# Pasa_Bajos.net
KiCad netlist of a schematic drawn in Altium Designer
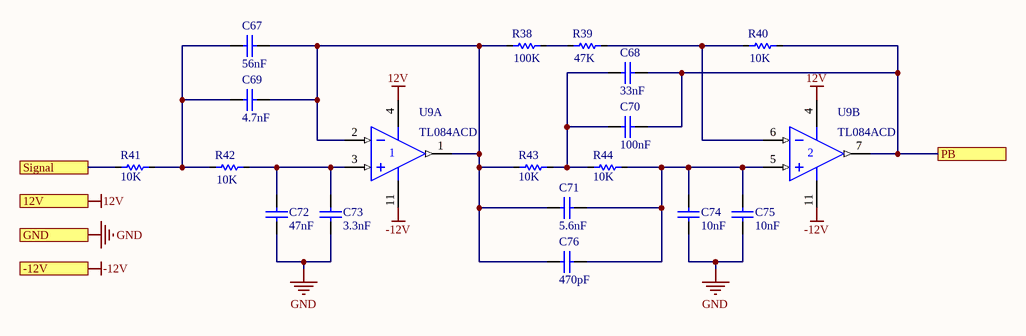
[diagram p0: Pasa Bajos.SchDoc]

(export (version "E")
  (design (tool "Eeschema 10.0.6"))
  (components
    (comp (ref "C67")
      (value "Cap Ceramico Disco")
      (footprint "cap 25")
      (description "Capacitor Ceramico de Insercion")
      (fields (field (name "VALOR") "56nF"))
      (libsource (lib "RUF-Dispositivos-Grales") (part "Cap Ceramico Disco"))
    )
    (comp (ref "C68")
      (value "Cap Ceramico Disco")
      (footprint "cap 10")
      (description "Capacitor Ceramico de Insercion")
      (fields (field (name "VALOR") "33nF"))
      (libsource (lib "RUF-Dispositivos-Grales") (part "Cap Ceramico Disco"))
    )
    (comp (ref "C69")
      (value "Cap Ceramico Disco")
      (footprint "cap 10")
      (description "Capacitor Ceramico de Insercion")
      (fields (field (name "VALOR") "4.7nF"))
      (libsource (lib "RUF-Dispositivos-Grales") (part "Cap Ceramico Disco"))
    )
    (comp (ref "C70")
      (value "Cap Ceramico Disco")
      (footprint "CAP DISCO 200mil")
      (description "Capacitor Ceramico de Insercion")
      (fields (field (name "VALOR") "100nF"))
      (libsource (lib "RUF-Dispositivos-Grales") (part "Cap Ceramico Disco"))
    )
    (comp (ref "C71")
      (value "Cap Ceramico Disco")
      (footprint "CAP DISCO 200mil")
      (description "Capacitor Ceramico de Insercion")
      (fields (field (name "VALOR") "5.6nF"))
      (libsource (lib "RUF-Dispositivos-Grales") (part "Cap Ceramico Disco"))
    )
    (comp (ref "C72")
      (value "Cap Ceramico Disco")
      (footprint "cap 10")
      (description "Capacitor Ceramico de Insercion")
      (fields (field (name "VALOR") "47nF"))
      (libsource (lib "RUF-Dispositivos-Grales") (part "Cap Ceramico Disco"))
    )
    (comp (ref "C73")
      (value "Cap Ceramico Disco")
      (footprint "CAP DISCO 200mil")
      (description "Capacitor Ceramico de Insercion")
      (fields (field (name "VALOR") "3.3nF"))
      (libsource (lib "RUF-Dispositivos-Grales") (part "Cap Ceramico Disco"))
    )
    (comp (ref "C74")
      (value "Cap Ceramico Disco")
      (footprint "CAP DISCO 200mil")
      (description "Capacitor Ceramico de Insercion")
      (fields (field (name "VALOR") "10nF"))
      (libsource (lib "RUF-Dispositivos-Grales") (part "Cap Ceramico Disco"))
    )
    (comp (ref "C75")
      (value "Cap Ceramico Disco")
      (footprint "CAP DISCO 200mil")
      (description "Capacitor Ceramico de Insercion")
      (fields (field (name "VALOR") "10nF"))
      (libsource (lib "RUF-Dispositivos-Grales") (part "Cap Ceramico Disco"))
    )
    (comp (ref "C76")
      (value "Cap Ceramico Disco")
      (footprint "CAP DISCO 200mil")
      (description "Capacitor Ceramico de Insercion")
      (fields (field (name "VALOR") "470pF"))
      (libsource (lib "RUF-Dispositivos-Grales") (part "Cap Ceramico Disco"))
    )
    (comp (ref "R38")
      (value "Res SMD")
      (footprint "RES AXIAL 400mil")
      (description "Res Smd")
      (fields (field (name "VALOR") "100K"))
      (libsource (lib "RUF-Dispositivos-Grales") (part "Res SMD"))
    )
    (comp (ref "R39")
      (value "Res SMD")
      (footprint "1206 resistor")
      (description "Res Smd")
      (fields (field (name "VALOR") "47K"))
      (libsource (lib "RUF-Dispositivos-Grales") (part "Res SMD"))
    )
    (comp (ref "R40")
      (value "Res SMD")
      (footprint "1206 resistor")
      (description "Res Smd")
      (fields (field (name "VALOR") "10K"))
      (libsource (lib "RUF-Dispositivos-Grales") (part "Res SMD"))
    )
    (comp (ref "R41")
      (value "Res SMD")
      (footprint "1206 resistor")
      (description "Res Smd")
      (fields (field (name "VALOR") "10K"))
      (libsource (lib "RUF-Dispositivos-Grales") (part "Res SMD"))
    )
    (comp (ref "R42")
      (value "Res SMD")
      (footprint "1206 resistor")
      (description "Res Smd")
      (fields (field (name "VALOR") "10K"))
      (libsource (lib "RUF-Dispositivos-Grales") (part "Res SMD"))
    )
    (comp (ref "R43")
      (value "Res SMD")
      (footprint "1206 resistor")
      (description "Res Smd")
      (fields (field (name "VALOR") "10K"))
      (libsource (lib "RUF-Dispositivos-Grales") (part "Res SMD"))
    )
    (comp (ref "R44")
      (value "Res SMD")
      (footprint "1206 resistor")
      (description "Res Smd")
      (fields (field (name "VALOR") "10K"))
      (libsource (lib "RUF-Dispositivos-Grales") (part "Res SMD"))
    )
    (comp (ref "U9")
      (value "TL084ACD")
      (footprint "751A-02_N")
      (description "JFET-Input Operational Amplifier")
      (fields (field (name "PUBLISHER") "Altium Limited"))
      (libsource (lib "Motorola Amplifier Operational Amplifier") (part "TL084ACD"))
    )
  )
  (nets
    (net (code "1") (name "-12V") (class "Default")
      (node (ref "U9") (pin "11") (pinfunction "V-_11") (pintype "power_in"))
    )
    (net (code "2") (name "/PB") (class "Default")
      (node (ref "C68") (pin "2") (pinfunction "2_2") (pintype "passive"))
      (node (ref "C70") (pin "2") (pinfunction "2_2") (pintype "passive"))
      (node (ref "R40") (pin "2") (pinfunction "2_2") (pintype "passive"))
      (node (ref "U9") (pin "7") (pinfunction "OUT_7") (pintype "output"))
    )
    (net (code "3") (name "/Signal") (class "Default")
      (node (ref "R41") (pin "1") (pinfunction "1_1") (pintype "passive"))
    )
    (net (code "4") (name "12V") (class "Default")
      (node (ref "U9") (pin "4") (pinfunction "V+_4") (pintype "power_in"))
    )
    (net (code "5") (name "GND") (class "Default")
      (node (ref "C72") (pin "1") (pinfunction "1_1") (pintype "passive"))
      (node (ref "C73") (pin "1") (pinfunction "1_1") (pintype "passive"))
      (node (ref "C74") (pin "2") (pinfunction "2_2") (pintype "passive"))
      (node (ref "C75") (pin "2") (pinfunction "2_2") (pintype "passive"))
    )
    (net (code "6") (name "Net-(C67-Pad2)") (class "Default")
      (node (ref "C67") (pin "2") (pinfunction "2_2") (pintype "passive"))
      (node (ref "C69") (pin "2") (pinfunction "2_2") (pintype "passive"))
      (node (ref "R41") (pin "2") (pinfunction "2_2") (pintype "passive"))
      (node (ref "R42") (pin "1") (pinfunction "1_1") (pintype "passive"))
    )
    (net (code "7") (name "Net-(C68-Pad1)") (class "Default")
      (node (ref "C68") (pin "1") (pinfunction "1_1") (pintype "passive"))
      (node (ref "C70") (pin "1") (pinfunction "1_1") (pintype "passive"))
      (node (ref "R43") (pin "2") (pinfunction "2_2") (pintype "passive"))
      (node (ref "R44") (pin "1") (pinfunction "1_1") (pintype "passive"))
    )
    (net (code "8") (name "Net-(R38-Pad2)") (class "Default")
      (node (ref "R38") (pin "2") (pinfunction "2_2") (pintype "passive"))
      (node (ref "R39") (pin "1") (pinfunction "1_1") (pintype "passive"))
    )
    (net (code "9") (name "Net-(U9A-IN+)") (class "Default")
      (node (ref "C72") (pin "2") (pinfunction "2_2") (pintype "passive"))
      (node (ref "C73") (pin "2") (pinfunction "2_2") (pintype "passive"))
      (node (ref "R42") (pin "2") (pinfunction "2_2") (pintype "passive"))
      (node (ref "U9") (pin "3") (pinfunction "IN+_3") (pintype "input"))
    )
    (net (code "10") (name "Net-(U9A-IN-)") (class "Default")
      (node (ref "C67") (pin "1") (pinfunction "1_1") (pintype "passive"))
      (node (ref "C69") (pin "1") (pinfunction "1_1") (pintype "passive"))
      (node (ref "C71") (pin "2") (pinfunction "2_2") (pintype "passive"))
      (node (ref "C76") (pin "2") (pinfunction "2_2") (pintype "passive"))
      (node (ref "R38") (pin "1") (pinfunction "1_1") (pintype "passive"))
      (node (ref "R43") (pin "1") (pinfunction "1_1") (pintype "passive"))
      (node (ref "U9") (pin "1") (pinfunction "OUT_1") (pintype "output"))
      (node (ref "U9") (pin "2") (pinfunction "IN-_2") (pintype "input"))
    )
    (net (code "11") (name "Net-(U9B-IN+)") (class "Default")
      (node (ref "C71") (pin "1") (pinfunction "1_1") (pintype "passive"))
      (node (ref "C74") (pin "1") (pinfunction "1_1") (pintype "passive"))
      (node (ref "C75") (pin "1") (pinfunction "1_1") (pintype "passive"))
      (node (ref "C76") (pin "1") (pinfunction "1_1") (pintype "passive"))
      (node (ref "R44") (pin "2") (pinfunction "2_2") (pintype "passive"))
      (node (ref "U9") (pin "5") (pinfunction "IN+_5") (pintype "input"))
    )
    (net (code "12") (name "Net-(U9B-IN-)") (class "Default")
      (node (ref "R39") (pin "2") (pinfunction "2_2") (pintype "passive"))
      (node (ref "R40") (pin "1") (pinfunction "1_1") (pintype "passive"))
      (node (ref "U9") (pin "6") (pinfunction "IN-_6") (pintype "input"))
    )
  )
)
